# LEDs.net
KiCad netlist of a schematic drawn in Altium Designer
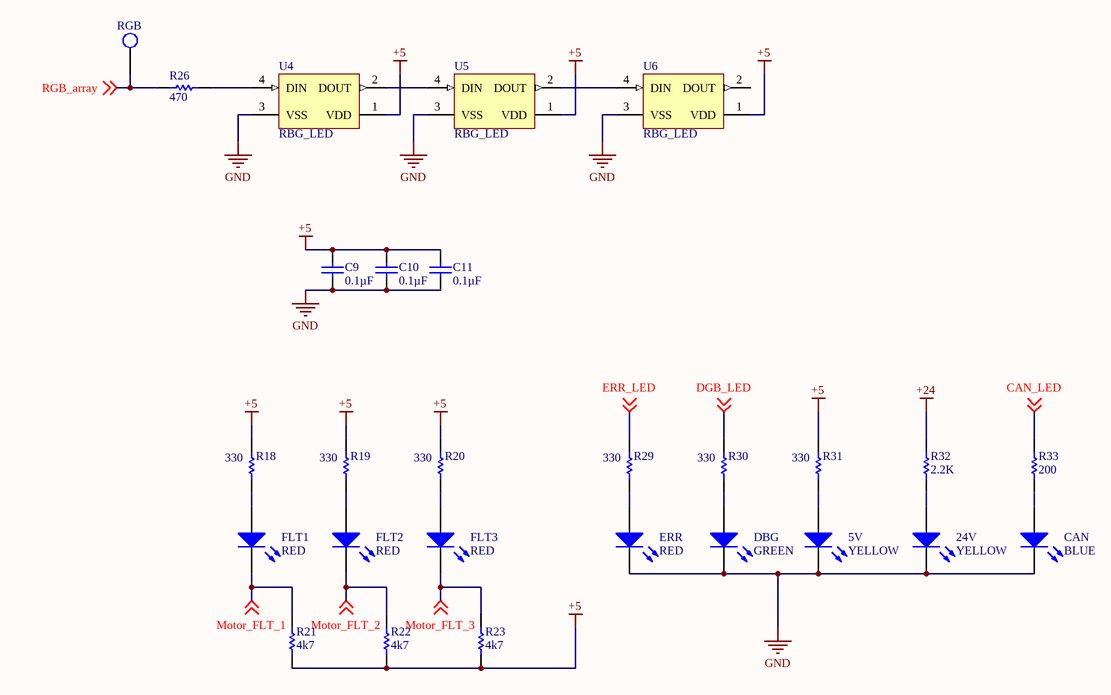
[diagram p0: LEDs.SchDoc]

(export (version "E")
  (design (tool "Eeschema 10.0.6"))
  (components
    (comp (ref "5V")
      (value "YELLOW")
      (footprint "0805_A")
      (description "Standard 0805 LED")
      (fields (field (name "MANUFACTURER") "Wuerth Elektronik") (field (name "PARTNUMBER") "150080SS75000"))
      (libsource (lib "Husky Robotics Standard Library 2019-2020") (part "LED"))
    )
    (comp (ref "24V")
      (value "YELLOW")
      (footprint "0805_A")
      (description "Standard 0805 LED")
      (fields (field (name "MANUFACTURER") "Wuerth Elektronik") (field (name "PARTNUMBER") "150080SS75000"))
      (libsource (lib "Husky Robotics Standard Library 2019-2020") (part "LED"))
    )
    (comp (ref "C9")
      (value "Capacitor 0805")
      (footprint "Cap 0805")
      (description "Standard Capacitor")
      (fields (field (name "MANUFACTURER") "AVX") (field (name "CAPACITANCE") "0.1µF"))
      (libsource (lib "Standard Cap") (part "Capacitor 0805"))
    )
    (comp (ref "C10")
      (value "Capacitor 0805")
      (footprint "Cap 0805")
      (description "Standard Capacitor")
      (fields (field (name "MANUFACTURER") "AVX") (field (name "CAPACITANCE") "0.1µF"))
      (libsource (lib "Standard Cap") (part "Capacitor 0805"))
    )
    (comp (ref "C11")
      (value "Capacitor 0805")
      (footprint "Cap 0805")
      (description "Standard Capacitor")
      (fields (field (name "MANUFACTURER") "AVX") (field (name "CAPACITANCE") "0.1µF"))
      (libsource (lib "Standard Cap") (part "Capacitor 0805"))
    )
    (comp (ref "CAN")
      (value "BLUE")
      (footprint "0805_A")
      (description "Standard 0805 LED")
      (fields (field (name "MANUFACTURER") "Wuerth Elektronik") (field (name "PARTNUMBER") "150080SS75000"))
      (libsource (lib "Husky Robotics Standard Library 2019-2020") (part "LED"))
    )
    (comp (ref "DBG")
      (value "GREEN")
      (footprint "0805_A")
      (description "Standard 0805 LED")
      (fields (field (name "MANUFACTURER") "Wuerth Elektronik") (field (name "PARTNUMBER") "150080SS75000"))
      (libsource (lib "Husky Robotics Standard Library 2019-2020") (part "LED"))
    )
    (comp (ref "ERR")
      (value "RED")
      (footprint "0805_A")
      (description "Standard 0805 LED")
      (fields (field (name "MANUFACTURER") "Wuerth Elektronik") (field (name "PARTNUMBER") "150080SS75000"))
      (libsource (lib "Husky Robotics Standard Library 2019-2020") (part "LED"))
    )
    (comp (ref "FLT1")
      (value "RED")
      (footprint "0805_A")
      (description "Standard 0805 LED")
      (fields (field (name "MANUFACTURER") "Wuerth Elektronik") (field (name "PARTNUMBER") "150080SS75000"))
      (libsource (lib "Husky Robotics Standard Library 2019-2020") (part "LED"))
    )
    (comp (ref "FLT2")
      (value "RED")
      (footprint "0805_A")
      (description "Standard 0805 LED")
      (fields (field (name "MANUFACTURER") "Wuerth Elektronik") (field (name "PARTNUMBER") "150080SS75000"))
      (libsource (lib "Husky Robotics Standard Library 2019-2020") (part "LED"))
    )
    (comp (ref "FLT3")
      (value "RED")
      (footprint "0805_A")
      (description "Standard 0805 LED")
      (fields (field (name "MANUFACTURER") "Wuerth Elektronik") (field (name "PARTNUMBER") "150080SS75000"))
      (libsource (lib "Husky Robotics Standard Library 2019-2020") (part "LED"))
    )
    (comp (ref "R18")
      (value "330")
      (footprint "RESC0805(2012)_N")
      (description "Generic 0805 Resistor")
      (fields (field (name "TOLERANCE") "5 %") (field (name "POWER") "0.125 W"))
      (libsource (lib "Husky Robotics Standard Library 2019-2020") (part "Resistor 0805"))
    )
    (comp (ref "R19")
      (value "330")
      (footprint "RESC0805(2012)_N")
      (description "Generic 0805 Resistor")
      (fields (field (name "TOLERANCE") "5 %") (field (name "POWER") "0.125 W"))
      (libsource (lib "Husky Robotics Standard Library 2019-2020") (part "Resistor 0805"))
    )
    (comp (ref "R20")
      (value "330")
      (footprint "RESC0805(2012)_N")
      (description "Generic 0805 Resistor")
      (fields (field (name "TOLERANCE") "5 %") (field (name "POWER") "0.125 W"))
      (libsource (lib "Husky Robotics Standard Library 2019-2020") (part "Resistor 0805"))
    )
    (comp (ref "R21")
      (value "4k7")
      (footprint "RESC0805(2012)_N")
      (description "Generic 0805 Resistor")
      (fields (field (name "TOLERANCE") "5 %") (field (name "POWER") "0.125 W"))
      (libsource (lib "Husky Robotics Standard Library 2019-2020") (part "Resistor 0805"))
    )
    (comp (ref "R22")
      (value "4k7")
      (footprint "RESC0805(2012)_N")
      (description "Generic 0805 Resistor")
      (fields (field (name "TOLERANCE") "5 %") (field (name "POWER") "0.125 W"))
      (libsource (lib "Husky Robotics Standard Library 2019-2020") (part "Resistor 0805"))
    )
    (comp (ref "R23")
      (value "4k7")
      (footprint "RESC0805(2012)_N")
      (description "Generic 0805 Resistor")
      (fields (field (name "TOLERANCE") "5 %") (field (name "POWER") "0.125 W"))
      (libsource (lib "Husky Robotics Standard Library 2019-2020") (part "Resistor 0805"))
    )
    (comp (ref "R26")
      (value "470")
      (footprint "RESC0805(2012)_N")
      (description "Generic 0805 Resistor")
      (fields (field (name "TOLERANCE") "5 %") (field (name "POWER") "0.125 W"))
      (libsource (lib "Husky Robotics Standard Library 2019-2020") (part "Resistor 0805"))
    )
    (comp (ref "R29")
      (value "330")
      (footprint "RESC0805(2012)_N")
      (description "Generic 0805 Resistor")
      (fields (field (name "TOLERANCE") "5 %") (field (name "POWER") "0.125 W"))
      (libsource (lib "Husky Robotics Standard Library 2019-2020") (part "Resistor 0805"))
    )
    (comp (ref "R30")
      (value "330")
      (footprint "RESC0805(2012)_N")
      (description "Generic 0805 Resistor")
      (fields (field (name "TOLERANCE") "5 %") (field (name "POWER") "0.125 W"))
      (libsource (lib "Husky Robotics Standard Library 2019-2020") (part "Resistor 0805"))
    )
    (comp (ref "R31")
      (value "330")
      (footprint "RESC0805(2012)_N")
      (description "Generic 0805 Resistor")
      (fields (field (name "TOLERANCE") "5 %") (field (name "POWER") "0.125 W"))
      (libsource (lib "Husky Robotics Standard Library 2019-2020") (part "Resistor 0805"))
    )
    (comp (ref "R32")
      (value "2.2K")
      (footprint "RESC0805(2012)_N")
      (description "Generic 0805 Resistor")
      (fields (field (name "TOLERANCE") "5 %") (field (name "POWER") "0.125 W"))
      (libsource (lib "Husky Robotics Standard Library 2019-2020") (part "Resistor 0805"))
    )
    (comp (ref "R33")
      (value "200")
      (footprint "RESC0805(2012)_N")
      (description "Generic 0805 Resistor")
      (fields (field (name "TOLERANCE") "5 %") (field (name "POWER") "0.125 W"))
      (libsource (lib "Husky Robotics Standard Library 2019-2020") (part "Resistor 0805"))
    )
    (comp (ref "RGB")
      (value "Test Point")
      (footprint "Test Point Through-hole")
      (libsource (lib "Husky Robotics Standard Library 2019-2020") (part "Test Point"))
    )
    (comp (ref "U4")
      (value "RBG_LED")
      (footprint "RGB_LED_1")
      (description "LED ADAI-WS2812B-4")
      (libsource (lib "Husky Robotics Standard Library 2019-2020") (part "RBG_LED"))
    )
    (comp (ref "U5")
      (value "RBG_LED")
      (footprint "RGB_LED_1")
      (description "LED ADAI-WS2812B-4")
      (libsource (lib "Husky Robotics Standard Library 2019-2020") (part "RBG_LED"))
    )
    (comp (ref "U6")
      (value "RBG_LED")
      (footprint "RGB_LED_1")
      (description "LED ADAI-WS2812B-4")
      (libsource (lib "Husky Robotics Standard Library 2019-2020") (part "RBG_LED"))
    )
  )
  (nets
    (net (code "1") (name "+5") (class "Default")
      (node (ref "C10") (pin "2") (pinfunction "2_2") (pintype "passive"))
      (node (ref "C11") (pin "2") (pinfunction "2_2") (pintype "passive"))
      (node (ref "C9") (pin "2") (pinfunction "2_2") (pintype "passive"))
      (node (ref "R18") (pin "2") (pinfunction "2_2") (pintype "passive"))
      (node (ref "R19") (pin "2") (pinfunction "2_2") (pintype "passive"))
      (node (ref "R20") (pin "2") (pinfunction "2_2") (pintype "passive"))
      (node (ref "R21") (pin "1") (pinfunction "1_1") (pintype "passive"))
      (node (ref "R22") (pin "1") (pinfunction "1_1") (pintype "passive"))
      (node (ref "R23") (pin "1") (pinfunction "1_1") (pintype "passive"))
      (node (ref "R31") (pin "2") (pinfunction "2_2") (pintype "passive"))
      (node (ref "U4") (pin "1") (pinfunction "VDD_1") (pintype "power_in"))
      (node (ref "U5") (pin "1") (pinfunction "VDD_1") (pintype "power_in"))
      (node (ref "U6") (pin "1") (pinfunction "VDD_1") (pintype "power_in"))
    )
    (net (code "2") (name "+24") (class "Default")
      (node (ref "R32") (pin "2") (pinfunction "2_2") (pintype "passive"))
    )
    (net (code "3") (name "CAN_LED") (class "Default")
      (node (ref "R33") (pin "2") (pinfunction "2_2") (pintype "passive"))
    )
    (net (code "4") (name "DGB_LED") (class "Default")
      (node (ref "R30") (pin "2") (pinfunction "2_2") (pintype "passive"))
    )
    (net (code "5") (name "ERR_LED") (class "Default")
      (node (ref "R29") (pin "2") (pinfunction "2_2") (pintype "passive"))
    )
    (net (code "6") (name "GND") (class "Default")
      (node (ref "24V") (pin "1") (pinfunction "K_1") (pintype "passive"))
      (node (ref "5V") (pin "1") (pinfunction "K_1") (pintype "passive"))
      (node (ref "C10") (pin "1") (pinfunction "1_1") (pintype "passive"))
      (node (ref "C11") (pin "1") (pinfunction "1_1") (pintype "passive"))
      (node (ref "C9") (pin "1") (pinfunction "1_1") (pintype "passive"))
      (node (ref "CAN") (pin "1") (pinfunction "K_1") (pintype "passive"))
      (node (ref "DBG") (pin "1") (pinfunction "K_1") (pintype "passive"))
      (node (ref "ERR") (pin "1") (pinfunction "K_1") (pintype "passive"))
      (node (ref "U4") (pin "3") (pinfunction "VSS_3") (pintype "power_in"))
      (node (ref "U5") (pin "3") (pinfunction "VSS_3") (pintype "power_in"))
      (node (ref "U6") (pin "3") (pinfunction "VSS_3") (pintype "power_in"))
    )
    (net (code "7") (name "Motor_FLT_1") (class "Default")
      (node (ref "FLT1") (pin "1") (pinfunction "K_1") (pintype "passive"))
      (node (ref "R21") (pin "2") (pinfunction "2_2") (pintype "passive"))
    )
    (net (code "8") (name "Motor_FLT_2") (class "Default")
      (node (ref "FLT2") (pin "1") (pinfunction "K_1") (pintype "passive"))
      (node (ref "R22") (pin "2") (pinfunction "2_2") (pintype "passive"))
    )
    (net (code "9") (name "Motor_FLT_3") (class "Default")
      (node (ref "FLT3") (pin "1") (pinfunction "K_1") (pintype "passive"))
      (node (ref "R23") (pin "2") (pinfunction "2_2") (pintype "passive"))
    )
    (net (code "10") (name "Net-(5V-A)") (class "Default")
      (node (ref "5V") (pin "2") (pinfunction "A_2") (pintype "passive"))
      (node (ref "R31") (pin "1") (pinfunction "1_1") (pintype "passive"))
    )
    (net (code "11") (name "Net-(24V-A)") (class "Default")
      (node (ref "24V") (pin "2") (pinfunction "A_2") (pintype "passive"))
      (node (ref "R32") (pin "1") (pinfunction "1_1") (pintype "passive"))
    )
    (net (code "12") (name "Net-(CAN-A)") (class "Default")
      (node (ref "CAN") (pin "2") (pinfunction "A_2") (pintype "passive"))
      (node (ref "R33") (pin "1") (pinfunction "1_1") (pintype "passive"))
    )
    (net (code "13") (name "Net-(DBG-A)") (class "Default")
      (node (ref "DBG") (pin "2") (pinfunction "A_2") (pintype "passive"))
      (node (ref "R30") (pin "1") (pinfunction "1_1") (pintype "passive"))
    )
    (net (code "14") (name "Net-(ERR-A)") (class "Default")
      (node (ref "ERR") (pin "2") (pinfunction "A_2") (pintype "passive"))
      (node (ref "R29") (pin "1") (pinfunction "1_1") (pintype "passive"))
    )
    (net (code "15") (name "Net-(FLT1-A)") (class "Default")
      (node (ref "FLT1") (pin "2") (pinfunction "A_2") (pintype "passive"))
      (node (ref "R18") (pin "1") (pinfunction "1_1") (pintype "passive"))
    )
    (net (code "16") (name "Net-(FLT2-A)") (class "Default")
      (node (ref "FLT2") (pin "2") (pinfunction "A_2") (pintype "passive"))
      (node (ref "R19") (pin "1") (pinfunction "1_1") (pintype "passive"))
    )
    (net (code "17") (name "Net-(FLT3-A)") (class "Default")
      (node (ref "FLT3") (pin "2") (pinfunction "A_2") (pintype "passive"))
      (node (ref "R20") (pin "1") (pinfunction "1_1") (pintype "passive"))
    )
    (net (code "18") (name "Net-(U4-DIN)") (class "Default")
      (node (ref "R26") (pin "2") (pinfunction "2_2") (pintype "passive"))
      (node (ref "U4") (pin "4") (pinfunction "DIN_4") (pintype "input"))
    )
    (net (code "19") (name "Net-(U4-DOUT)") (class "Default")
      (node (ref "U4") (pin "2") (pinfunction "DOUT_2") (pintype "output"))
      (node (ref "U5") (pin "4") (pinfunction "DIN_4") (pintype "input"))
    )
    (net (code "20") (name "Net-(U5-DOUT)") (class "Default")
      (node (ref "U5") (pin "2") (pinfunction "DOUT_2") (pintype "output"))
      (node (ref "U6") (pin "4") (pinfunction "DIN_4") (pintype "input"))
    )
    (net (code "21") (name "RGB_array") (class "Default")
      (node (ref "R26") (pin "1") (pinfunction "1_1") (pintype "passive"))
      (node (ref "RGB") (pin "1") (pinfunction "1_1") (pintype "passive"))
    )
    (net (code "22") (name "unconnected-(U6-DOUT-Pad2)") (class "Default")
      (node (ref "U6") (pin "2") (pinfunction "DOUT_2") (pintype "output"))
    )
  )
)
